# HEXADECASPI_PSRAM.net
KiCad netlist of a schematic drawn in Altium Designer
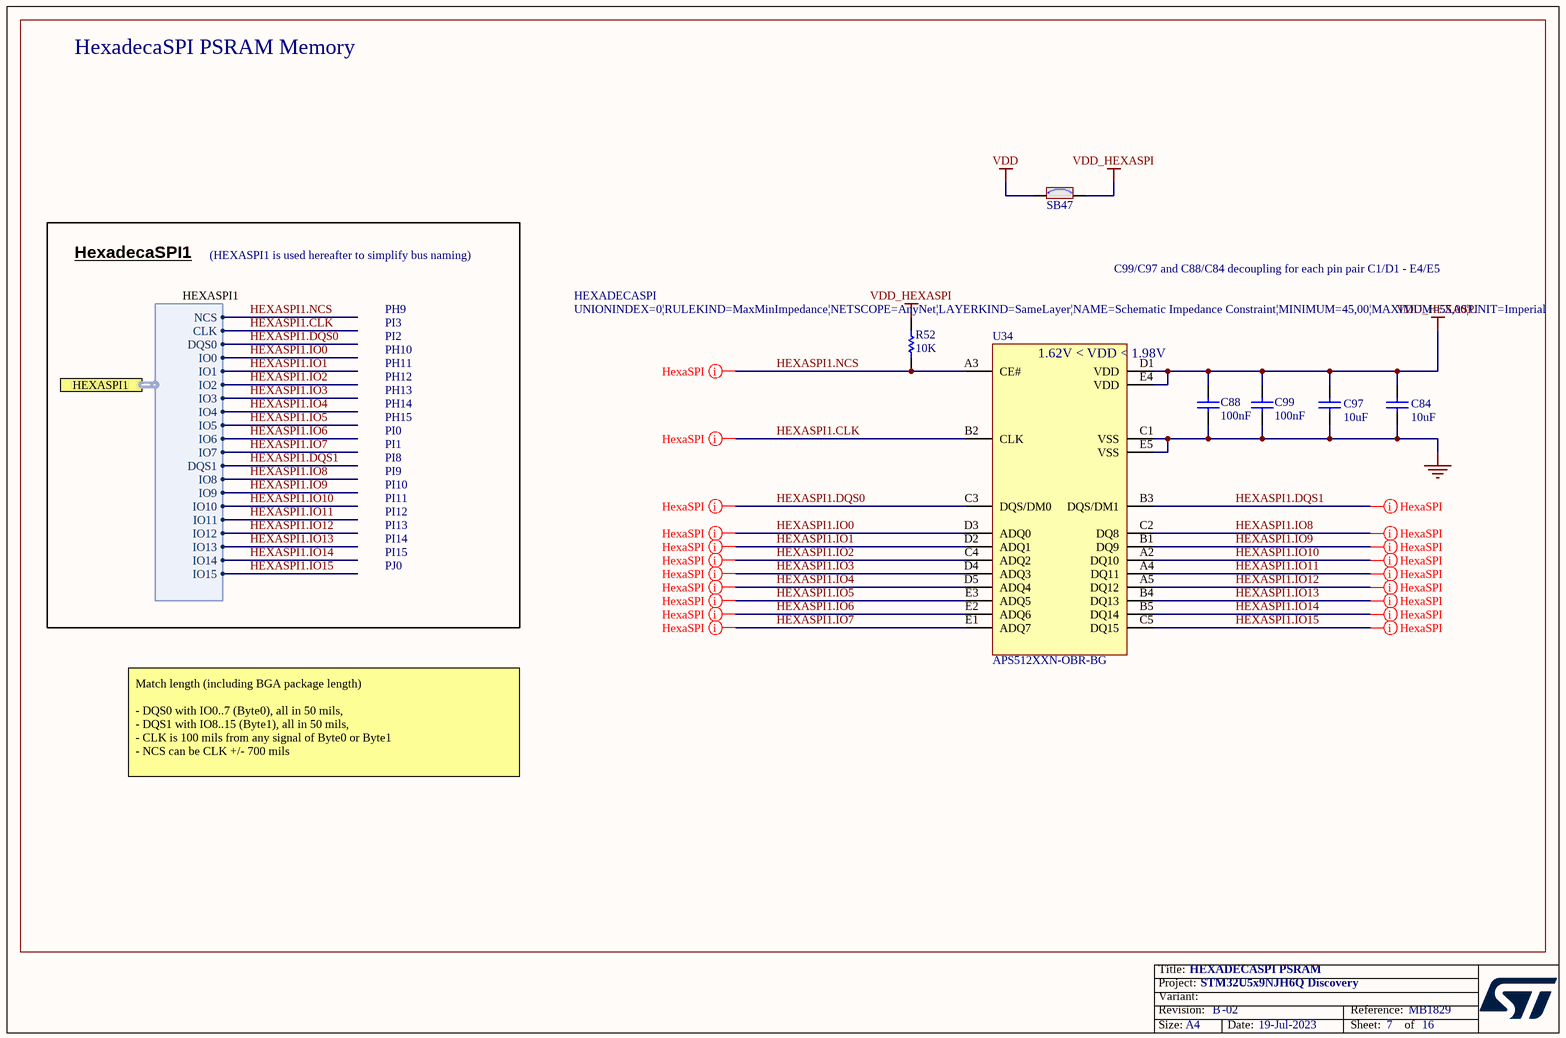
[diagram p0: HEXADECASPI_PSRAM.SchDoc]

(export (version "E")
  (design (tool "Eeschema 10.0.6"))
  (components
    (comp (ref "C84")
      (value "10uF")
      (footprint "MCD_PARTS:C0603_H0P8")
      (description "Capacitor, MLCC, 10uF, 10V, X5R, +/-10%, 0603, T=0.8mm")
      (fields
        (field (name "INTERNAL_PART_NUMBER") "MCD-02605")
        (field (name "MANUFACTURER_PART_NUMBER") "CC0603KRX5R6BB106")
      )
      (libsource (lib "MCD_PARTS_database") (part "Capacitor"))
    )
    (comp (ref "C88")
      (value "100nF")
      (footprint "MCD_PARTS:C0402")
      (description "Capacitor, MLCC, 100nF, 16V, X7R, +/-10%, 0402, T=0.5mm")
      (fields
        (field (name "INTERNAL_PART_NUMBER") "MCD-00006")
        (field (name "MANUFACTURER_PART_NUMBER") "CC0402KRX7R7BB104")
      )
      (libsource (lib "MCD_PARTS_database") (part "Capacitor"))
    )
    (comp (ref "C97")
      (value "10uF")
      (footprint "MCD_PARTS:C0603_H0P8")
      (description "Capacitor, MLCC, 10uF, 10V, X5R, +/-10%, 0603, T=0.8mm")
      (fields
        (field (name "INTERNAL_PART_NUMBER") "MCD-02605")
        (field (name "MANUFACTURER_PART_NUMBER") "CC0603KRX5R6BB106")
      )
      (libsource (lib "MCD_PARTS_database") (part "Capacitor"))
    )
    (comp (ref "C99")
      (value "100nF")
      (footprint "MCD_PARTS:C0402")
      (description "Capacitor, MLCC, 100nF, 16V, X7R, +/-10%, 0402, T=0.5mm")
      (fields
        (field (name "INTERNAL_PART_NUMBER") "MCD-00006")
        (field (name "MANUFACTURER_PART_NUMBER") "CC0402KRX7R7BB104")
      )
      (libsource (lib "MCD_PARTS_database") (part "Capacitor"))
    )
    (comp (ref "R52")
      (value "10K")
      (footprint "MCD_PARTS:R0402")
      (description "Resistor, 10K, 0402, +/-1%, 1/16W")
      (fields
        (field (name "INTERNAL_PART_NUMBER") "MCD-00053")
        (field (name "MANUFACTURER_PART_NUMBER") "RC0402FR-0710KL")
      )
      (libsource (lib "MCD_PARTS_database") (part "Resistor"))
    )
    (comp (ref "SB47")
      (value "SB_ON")
      (footprint "MCD_PARTS:SOLDER-BRIDGE_R0402-0R")
      (description "Solder Bridge 0402 ON")
      (fields
        (field (name "INTERNAL_PART_NUMBER") "MCD-01618")
        (field (name "MANUFACTURER_PART_NUMBER") "RC0402JR-070RL")
      )
      (libsource (lib "MCD_PARTS_database") (part "SB_ON"))
    )
    (comp (ref "U34")
      (value "APS512XXN-OBR-BG")
      (footprint "MCD_PARTS:ICC_BGA24_5X5-BALL-ARRAY_6X8_P1")
      (description "Memory,Hexa-SPI-PSRAM,512Mb,x8x16,200MHz,1.8V,DDR,BGA24, PASR LVCMOS")
      (fields
        (field (name "INTERNAL_PART_NUMBER") "MCD-02904")
        (field (name "MANUFACTURER") "AP MEMORY TECHNOLOGY CORP.")
      )
      (libsource (lib "MCD_PARTS_database") (part "APS256XXN-OBR-BG"))
    )
  )
  (nets
    (net (code "2") (name "/HEXASPI1.CLK") (class "Default")
      (node (ref "U34") (pin "B2") (pinfunction "CLK_B2") (pintype "passive"))
    )
    (net (code "3") (name "/HEXASPI1.DQS0") (class "Default")
      (node (ref "U34") (pin "C3") (pinfunction "DQS/DM0_C3") (pintype "passive"))
    )
    (net (code "4") (name "/HEXASPI1.DQS1") (class "Default")
      (node (ref "U34") (pin "B3") (pinfunction "DQS/DM1_B3") (pintype "passive"))
    )
    (net (code "5") (name "/HEXASPI1.IO0") (class "Default")
      (node (ref "U34") (pin "D3") (pinfunction "ADQ0_D3") (pintype "passive"))
    )
    (net (code "6") (name "/HEXASPI1.IO1") (class "Default")
      (node (ref "U34") (pin "D2") (pinfunction "ADQ1_D2") (pintype "passive"))
    )
    (net (code "7") (name "/HEXASPI1.IO2") (class "Default")
      (node (ref "U34") (pin "C4") (pinfunction "ADQ2_C4") (pintype "passive"))
    )
    (net (code "8") (name "/HEXASPI1.IO3") (class "Default")
      (node (ref "U34") (pin "D4") (pinfunction "ADQ3_D4") (pintype "passive"))
    )
    (net (code "9") (name "/HEXASPI1.IO4") (class "Default")
      (node (ref "U34") (pin "D5") (pinfunction "ADQ4_D5") (pintype "passive"))
    )
    (net (code "10") (name "/HEXASPI1.IO5") (class "Default")
      (node (ref "U34") (pin "E3") (pinfunction "ADQ5_E3") (pintype "passive"))
    )
    (net (code "11") (name "/HEXASPI1.IO6") (class "Default")
      (node (ref "U34") (pin "E2") (pinfunction "ADQ6_E2") (pintype "passive"))
    )
    (net (code "12") (name "/HEXASPI1.IO7") (class "Default")
      (node (ref "U34") (pin "E1") (pinfunction "ADQ7_E1") (pintype "passive"))
    )
    (net (code "13") (name "/HEXASPI1.IO8") (class "Default")
      (node (ref "U34") (pin "C2") (pinfunction "DQ8_C2") (pintype "passive"))
    )
    (net (code "14") (name "/HEXASPI1.IO9") (class "Default")
      (node (ref "U34") (pin "B1") (pinfunction "DQ9_B1") (pintype "passive"))
    )
    (net (code "15") (name "/HEXASPI1.IO10") (class "Default")
      (node (ref "U34") (pin "A2") (pinfunction "DQ10_A2") (pintype "passive"))
    )
    (net (code "16") (name "/HEXASPI1.IO11") (class "Default")
      (node (ref "U34") (pin "A4") (pinfunction "DQ11_A4") (pintype "passive"))
    )
    (net (code "17") (name "/HEXASPI1.IO12") (class "Default")
      (node (ref "U34") (pin "A5") (pinfunction "DQ12_A5") (pintype "passive"))
    )
    (net (code "18") (name "/HEXASPI1.IO13") (class "Default")
      (node (ref "U34") (pin "B4") (pinfunction "DQ13_B4") (pintype "passive"))
    )
    (net (code "19") (name "/HEXASPI1.IO14") (class "Default")
      (node (ref "U34") (pin "B5") (pinfunction "DQ14_B5") (pintype "passive"))
    )
    (net (code "20") (name "/HEXASPI1.IO15") (class "Default")
      (node (ref "U34") (pin "C5") (pinfunction "DQ15_C5") (pintype "passive"))
    )
    (net (code "21") (name "/HEXASPI1.NCS") (class "Default")
      (node (ref "R52") (pin "1") (pinfunction "1_1") (pintype "passive"))
      (node (ref "U34") (pin "A3") (pinfunction "CE#_A3") (pintype "passive"))
    )
    (net (code "23") (name "GND") (class "Default")
      (node (ref "C84") (pin "1") (pinfunction "1_1") (pintype "passive"))
      (node (ref "C88") (pin "1") (pinfunction "1_1") (pintype "passive"))
      (node (ref "C97") (pin "1") (pinfunction "1_1") (pintype "passive"))
      (node (ref "C99") (pin "1") (pinfunction "1_1") (pintype "passive"))
      (node (ref "U34") (pin "C1") (pinfunction "VSS_C1") (pintype "passive"))
      (node (ref "U34") (pin "E5") (pinfunction "VSS_E5") (pintype "passive"))
    )
    (net (code "24") (name "VDD") (class "Default")
      (node (ref "SB47") (pin "1") (pinfunction "1_1") (pintype "passive"))
    )
    (net (code "25") (name "VDD_HEXASPI") (class "Default")
      (node (ref "C84") (pin "2") (pinfunction "2_2") (pintype "passive"))
      (node (ref "C88") (pin "2") (pinfunction "2_2") (pintype "passive"))
      (node (ref "C97") (pin "2") (pinfunction "2_2") (pintype "passive"))
      (node (ref "C99") (pin "2") (pinfunction "2_2") (pintype "passive"))
      (node (ref "R52") (pin "2") (pinfunction "2_2") (pintype "passive"))
      (node (ref "SB47") (pin "2") (pinfunction "2_2") (pintype "passive"))
      (node (ref "U34") (pin "D1") (pinfunction "VDD_D1") (pintype "passive"))
      (node (ref "U34") (pin "E4") (pinfunction "VDD_E4") (pintype "passive"))
    )
  )
)
